# 7_EEPROM.net
KiCad netlist of a schematic drawn in Altium Designer
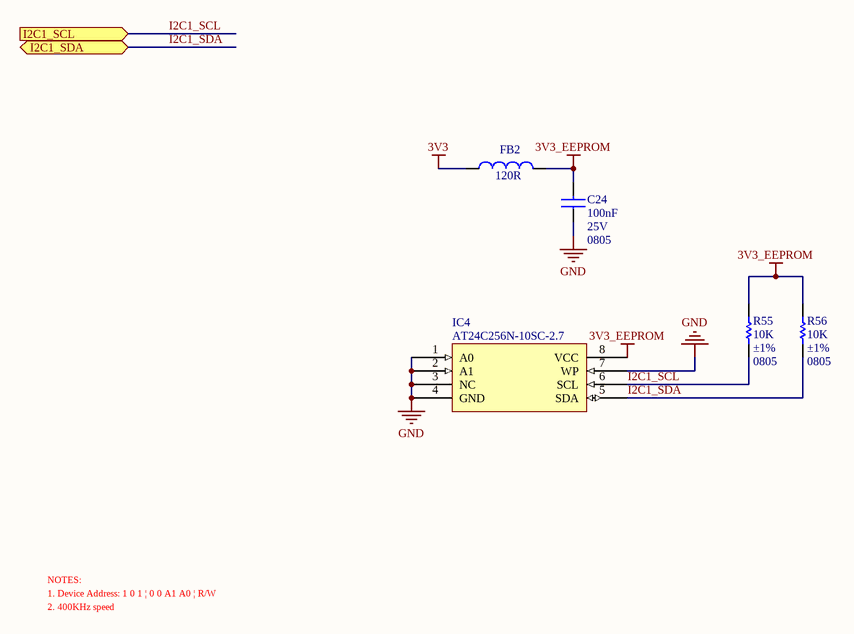
[diagram p0: 7.EEPROM.SchDoc]

(export (version "E")
  (design (tool "Eeschema 10.0.6"))
  (components
    (comp (ref "C24")
      (value "CAP_NP")
      (footprint "CAPC2012X100N_EIA0805")
      (description "CAP CER 0.1UF 25V X7R 0805")
      (fields
        (field (name "PART NUMBER") "SCAP00300093")
        (field (name "CAPACITANCE") "100nF")
        (field (name "TOLERANCE") "±10%")
        (field (name "VOLTAGE - RATED") "25V")
        (field (name "PACKAGE / CASE") "0805")
      )
      (libsource (lib "ComponentDatabase") (part "CAP_NP"))
    )
    (comp (ref "FB2")
      (value "BEAD")
      (footprint "FILC2012X100N_EIA0805")
      (description "FERRITE CHIP POWER 120 OHM SMD")
      (fields
        (field (name "PART NUMBER") "SFIL00005")
        (field (name "IMPEDANCE") "120R")
        (field (name "MANUFACTURER") "Laird-Signal Integrity Products")
      )
      (libsource (lib "ComponentDatabase") (part "BEAD"))
    )
    (comp (ref "IC4")
      (value "AT24C256")
      (footprint "SOIC127P600X175-8N")
      (description "IC EEPROM 256KBIT 1MHZ 8SOIC")
      (fields
        (field (name "PART NUMBER") "SMEM00019")
        (field (name "VOLTAGE") "2.7 V ~ 5.5 V")
        (field (name "MANUFACTURER PART NUMBER") "AT24C256N-10SC-2.7")
      )
      (libsource (lib "ComponentDatabase") (part "AT24C256"))
    )
    (comp (ref "R55")
      (value "RES")
      (footprint "RESC2013X65N_EIA0805")
      (description "RES SMD 10K OHM 1% 1/8W 0805")
      (fields
        (field (name "PART NUMBER") "SRES03010098")
        (field (name "RESISTANCE (OHM)") "10K")
        (field (name "TOLERANCE") "±1%")
        (field (name "PACKAGE / CASE") "0805")
        (field (name "MANUFACTURER") "Yageo")
      )
      (libsource (lib "ComponentDatabase") (part "RES"))
    )
    (comp (ref "R56")
      (value "RES")
      (footprint "RESC2013X65N_EIA0805")
      (description "RES SMD 10K OHM 1% 1/8W 0805")
      (fields
        (field (name "PART NUMBER") "SRES03010098")
        (field (name "RESISTANCE (OHM)") "10K")
        (field (name "TOLERANCE") "±1%")
        (field (name "PACKAGE / CASE") "0805")
        (field (name "MANUFACTURER") "Yageo")
      )
      (libsource (lib "ComponentDatabase") (part "RES"))
    )
  )
  (nets
    (net (code "1") (name "/I2C1_SCL") (class "Default")
      (node (ref "IC4") (pin "6") (pinfunction "SCL_6") (pintype "input"))
      (node (ref "R55") (pin "2") (pinfunction "2_2") (pintype "passive"))
    )
    (net (code "2") (name "/I2C1_SDA") (class "Default")
      (node (ref "IC4") (pin "5") (pinfunction "SDA_5") (pintype "bidirectional"))
      (node (ref "R56") (pin "2") (pinfunction "2_2") (pintype "passive"))
    )
    (net (code "3") (name "3V3") (class "Default")
      (node (ref "FB2") (pin "1") (pinfunction "1_1") (pintype "passive"))
    )
    (net (code "4") (name "3V3_EEPROM") (class "Default")
      (node (ref "C24") (pin "2") (pinfunction "2_2") (pintype "passive"))
      (node (ref "FB2") (pin "2") (pinfunction "2_2") (pintype "passive"))
      (node (ref "IC4") (pin "8") (pinfunction "VCC_8") (pintype "power_in"))
      (node (ref "R55") (pin "1") (pinfunction "1_1") (pintype "passive"))
      (node (ref "R56") (pin "1") (pinfunction "1_1") (pintype "passive"))
    )
    (net (code "5") (name "GND") (class "Default")
      (node (ref "C24") (pin "1") (pinfunction "1_1") (pintype "passive"))
      (node (ref "IC4") (pin "1") (pinfunction "A0_1") (pintype "input"))
      (node (ref "IC4") (pin "2") (pinfunction "A1_2") (pintype "input"))
      (node (ref "IC4") (pin "3") (pinfunction "NC_3") (pintype "passive"))
      (node (ref "IC4") (pin "4") (pinfunction "GND_4") (pintype "power_in"))
      (node (ref "IC4") (pin "7") (pinfunction "WP_7") (pintype "input"))
    )
  )
)
